# B138X.net
KiCad netlist of a schematic drawn in EAGLE
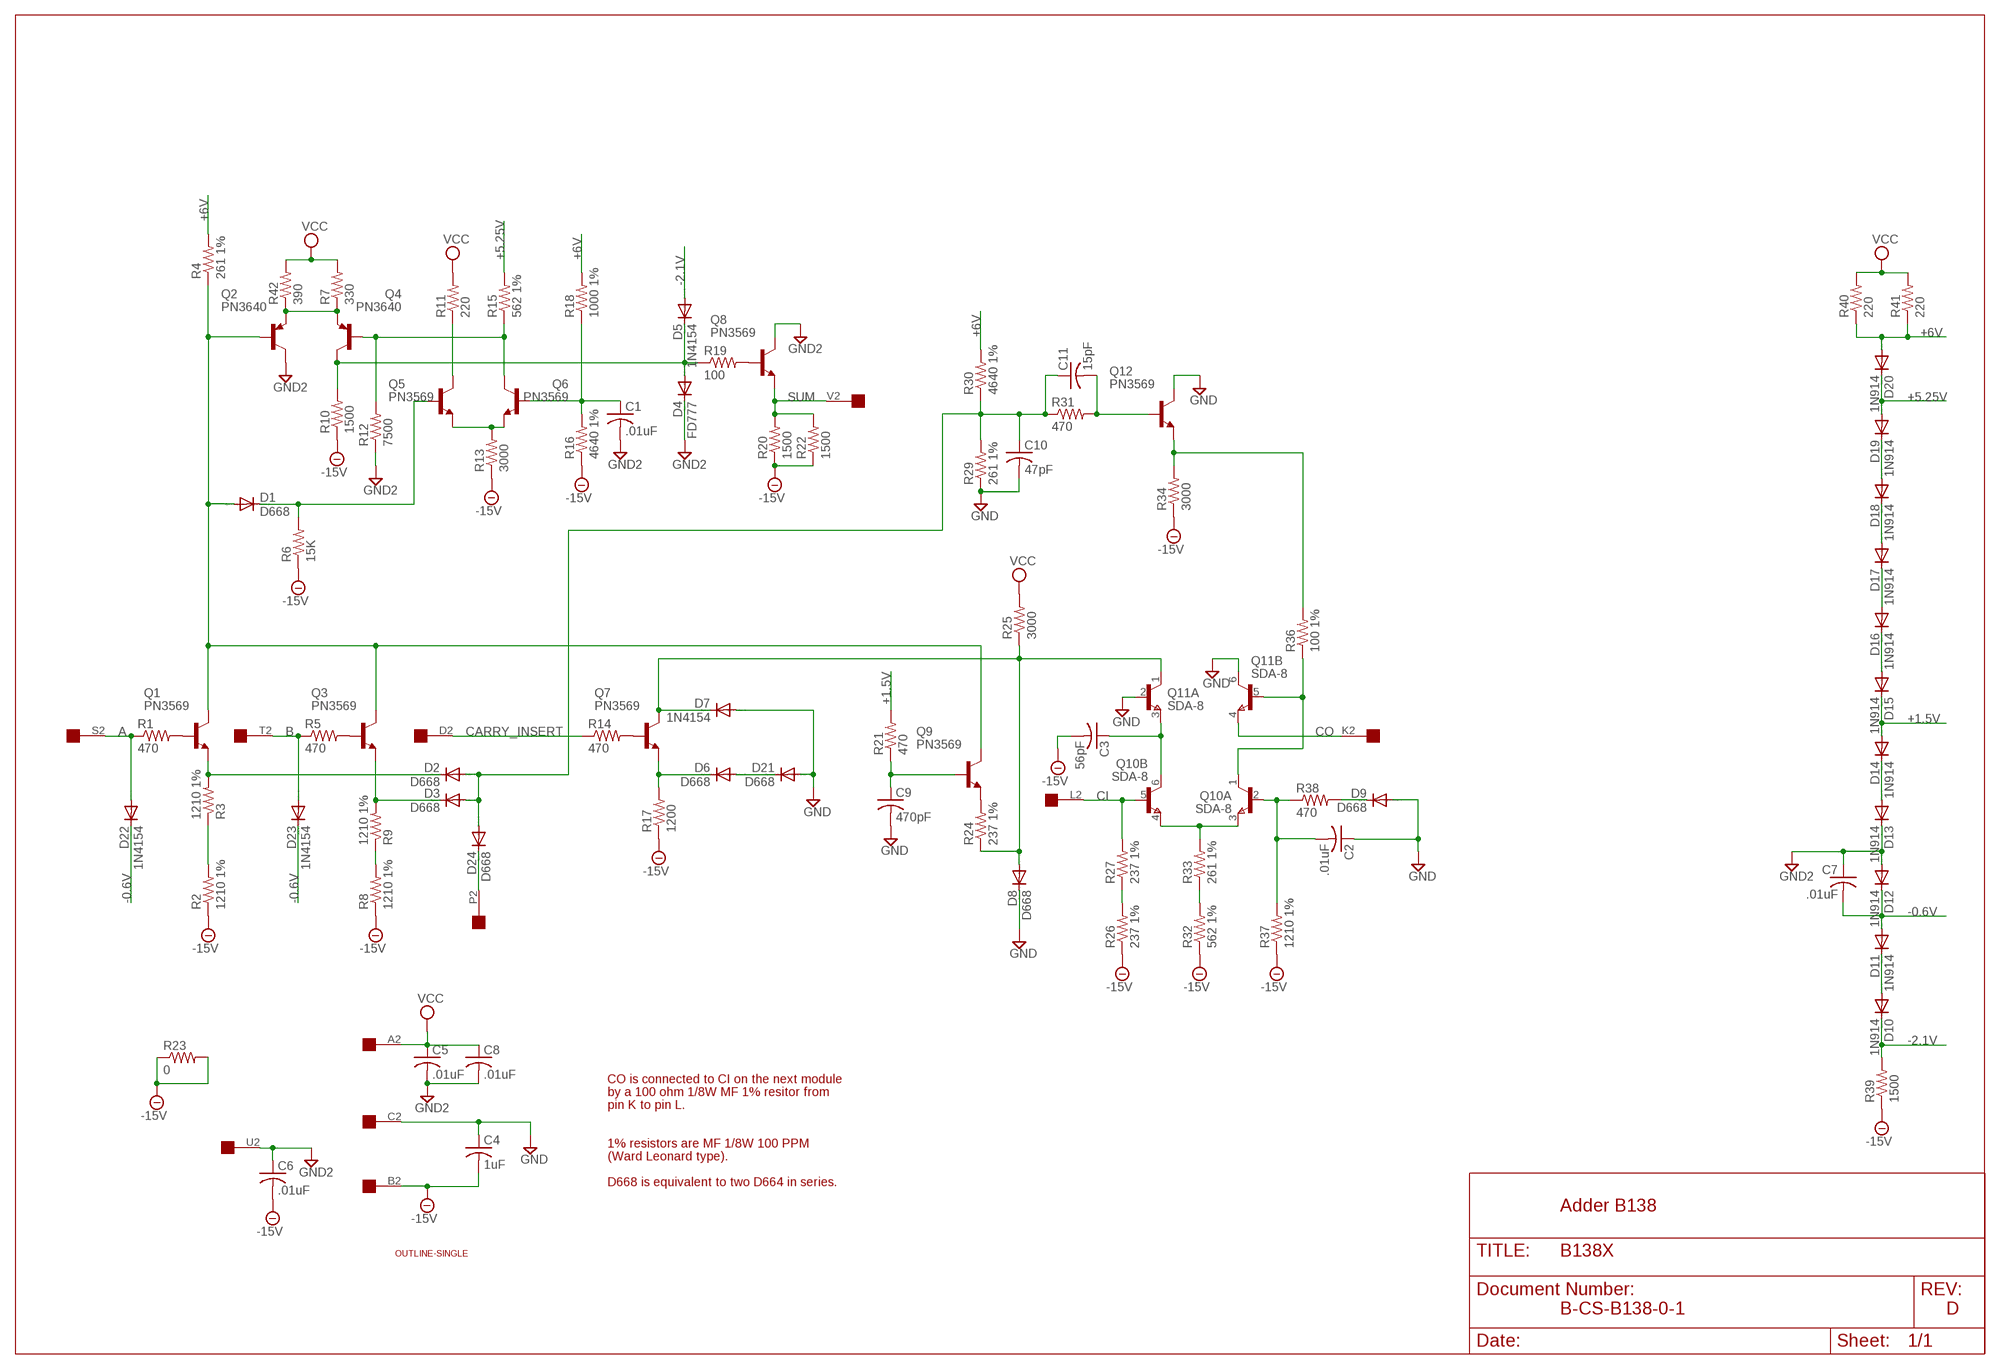
[diagram p0: schematic, sheet 1]

(export (version "E")
  (design (tool "Eeschema 10.0.6"))
  (components
    (comp (ref "C1")
      (value ".01uF")
      (footprint "eagle-import:C063-025X075")
      (libsource (lib "eagle-import") (part "C-US"))
    )
    (comp (ref "C2")
      (value ".01uF")
      (footprint "eagle-import:C063-025X075")
      (libsource (lib "eagle-import") (part "C-US"))
    )
    (comp (ref "C3")
      (value "56pF")
      (footprint "eagle-import:C063-025X075")
      (libsource (lib "eagle-import") (part "C-US"))
    )
    (comp (ref "C4")
      (value "1uF")
      (footprint "eagle-import:C102-043X133")
      (libsource (lib "eagle-import") (part "C-US102-043X133"))
    )
    (comp (ref "C5")
      (value ".01uF")
      (footprint "eagle-import:C063-025X075")
      (libsource (lib "eagle-import") (part "C-US"))
    )
    (comp (ref "C6")
      (value ".01uF")
      (footprint "eagle-import:C063-025X075")
      (libsource (lib "eagle-import") (part "C-US"))
    )
    (comp (ref "C7")
      (value ".01uF")
      (footprint "eagle-import:C063-025X075")
      (libsource (lib "eagle-import") (part "C-US"))
    )
    (comp (ref "C8")
      (value ".01uF")
      (footprint "eagle-import:C063-025X075")
      (libsource (lib "eagle-import") (part "C-US"))
    )
    (comp (ref "C9")
      (value "470pF")
      (footprint "eagle-import:C063-025X075")
      (libsource (lib "eagle-import") (part "C-US"))
    )
    (comp (ref "C10")
      (value "47pF")
      (footprint "eagle-import:C063-025X075")
      (libsource (lib "eagle-import") (part "C-US"))
    )
    (comp (ref "C11")
      (value "15pF")
      (footprint "eagle-import:C063-025X075")
      (libsource (lib "eagle-import") (part "C-US"))
    )
    (comp (ref "D1")
      (value "D668")
      (footprint "eagle-import:DO35-10")
      (libsource (lib "eagle-import") (part "DIODE-DO35-10"))
    )
    (comp (ref "D2")
      (value "D668")
      (footprint "eagle-import:DO35-10")
      (libsource (lib "eagle-import") (part "DIODE-DO35-10"))
    )
    (comp (ref "D3")
      (value "D668")
      (footprint "eagle-import:DO35-10")
      (libsource (lib "eagle-import") (part "DIODE-DO35-10"))
    )
    (comp (ref "D4")
      (value "FD777")
      (footprint "eagle-import:DO35-10")
      (libsource (lib "eagle-import") (part "DIODE-DO35-10"))
    )
    (comp (ref "D5")
      (value "1N4154")
      (footprint "eagle-import:DO35-10")
      (libsource (lib "eagle-import") (part "DIODE-DO35-10"))
    )
    (comp (ref "D6")
      (value "D668")
      (footprint "eagle-import:DO35-10")
      (libsource (lib "eagle-import") (part "DIODE-DO35-10"))
    )
    (comp (ref "D7")
      (value "1N4154")
      (footprint "eagle-import:DO35-10")
      (libsource (lib "eagle-import") (part "DIODE-DO35-10"))
    )
    (comp (ref "D8")
      (value "D668")
      (footprint "eagle-import:DO35-10")
      (libsource (lib "eagle-import") (part "DIODE-DO35-10"))
    )
    (comp (ref "D9")
      (value "D668")
      (footprint "eagle-import:DO35-10")
      (libsource (lib "eagle-import") (part "DIODE-DO35-10"))
    )
    (comp (ref "D10")
      (value "1N914")
      (footprint "eagle-import:DO35-10")
      (libsource (lib "eagle-import") (part "DIODE-DO35-10"))
    )
    (comp (ref "D11")
      (value "1N914")
      (footprint "eagle-import:DO35-10")
      (libsource (lib "eagle-import") (part "DIODE-DO35-10"))
    )
    (comp (ref "D12")
      (value "1N914")
      (footprint "eagle-import:DO35-10")
      (libsource (lib "eagle-import") (part "DIODE-DO35-10"))
    )
    (comp (ref "D13")
      (value "1N914")
      (footprint "eagle-import:DO35-10")
      (libsource (lib "eagle-import") (part "DIODE-DO35-10"))
    )
    (comp (ref "D14")
      (value "1N914")
      (footprint "eagle-import:DO35-10")
      (libsource (lib "eagle-import") (part "DIODE-DO35-10"))
    )
    (comp (ref "D15")
      (value "1N914")
      (footprint "eagle-import:DO35-10")
      (libsource (lib "eagle-import") (part "DIODE-DO35-10"))
    )
    (comp (ref "D16")
      (value "1N914")
      (footprint "eagle-import:DO35-10")
      (libsource (lib "eagle-import") (part "DIODE-DO35-10"))
    )
    (comp (ref "D17")
      (value "1N914")
      (footprint "eagle-import:DO35-10")
      (libsource (lib "eagle-import") (part "DIODE-DO35-10"))
    )
    (comp (ref "D18")
      (value "1N914")
      (footprint "eagle-import:DO35-10")
      (libsource (lib "eagle-import") (part "DIODE-DO35-10"))
    )
    (comp (ref "D19")
      (value "1N914")
      (footprint "eagle-import:DO35-10")
      (libsource (lib "eagle-import") (part "DIODE-DO35-10"))
    )
    (comp (ref "D20")
      (value "1N914")
      (footprint "eagle-import:DO35-10")
      (libsource (lib "eagle-import") (part "DIODE-DO35-10"))
    )
    (comp (ref "D21")
      (value "D668")
      (footprint "eagle-import:DO35-10")
      (libsource (lib "eagle-import") (part "DIODE-DO35-10"))
    )
    (comp (ref "D22")
      (value "1N4154")
      (footprint "eagle-import:DO35-10")
      (libsource (lib "eagle-import") (part "DIODE-DO35-10"))
    )
    (comp (ref "D23")
      (value "1N4154")
      (footprint "eagle-import:DO35-10")
      (libsource (lib "eagle-import") (part "DIODE-DO35-10"))
    )
    (comp (ref "D24")
      (value "D668")
      (footprint "eagle-import:DO35-10")
      (libsource (lib "eagle-import") (part "DIODE-DO35-10"))
    )
    (comp (ref "Q1")
      (value "PN3569")
      (footprint "eagle-import:TO5")
      (libsource (lib "eagle-import") (part "-NPN-TO5"))
    )
    (comp (ref "Q2")
      (value "PN3640")
      (footprint "eagle-import:TO5")
      (libsource (lib "eagle-import") (part "-PNP-TO5"))
    )
    (comp (ref "Q3")
      (value "PN3569")
      (footprint "eagle-import:TO5")
      (libsource (lib "eagle-import") (part "-NPN-TO5"))
    )
    (comp (ref "Q4")
      (value "PN3640")
      (footprint "eagle-import:TO5")
      (libsource (lib "eagle-import") (part "-PNP-TO5"))
    )
    (comp (ref "Q5")
      (value "PN3569")
      (footprint "eagle-import:TO5")
      (libsource (lib "eagle-import") (part "-NPN-TO5"))
    )
    (comp (ref "Q6")
      (value "PN3569")
      (footprint "eagle-import:TO5")
      (libsource (lib "eagle-import") (part "-NPN-TO5"))
    )
    (comp (ref "Q7")
      (value "PN3569")
      (footprint "eagle-import:TO5")
      (libsource (lib "eagle-import") (part "-NPN-TO5"))
    )
    (comp (ref "Q8")
      (value "PN3569")
      (footprint "eagle-import:TO5")
      (libsource (lib "eagle-import") (part "-NPN-TO5"))
    )
    (comp (ref "Q9")
      (value "PN3569")
      (footprint "eagle-import:TO5")
      (libsource (lib "eagle-import") (part "-NPN-TO5"))
    )
    (comp (ref "Q10")
      (value "SDA-8")
      (footprint "eagle-import:TO78")
      (libsource (lib "eagle-import") (part "MAT-02H"))
    )
    (comp (ref "Q11")
      (value "SDA-8")
      (footprint "eagle-import:TO78")
      (libsource (lib "eagle-import") (part "MAT-02H"))
    )
    (comp (ref "Q12")
      (value "PN3569")
      (footprint "eagle-import:TO5")
      (libsource (lib "eagle-import") (part "-NPN-TO5"))
    )
    (comp (ref "R1")
      (value "470")
      (footprint "eagle-import:0207_10")
      (libsource (lib "eagle-import") (part "R-US_0207/10"))
    )
    (comp (ref "R2")
      (value "1210 1%")
      (footprint "eagle-import:0207_15")
      (libsource (lib "eagle-import") (part "R-US_0207/15"))
    )
    (comp (ref "R3")
      (value "1210 1%")
      (footprint "eagle-import:0207_15")
      (libsource (lib "eagle-import") (part "R-US_0207/15"))
    )
    (comp (ref "R4")
      (value "261 1%")
      (footprint "eagle-import:0207_15")
      (libsource (lib "eagle-import") (part "R-US_0207/15"))
    )
    (comp (ref "R5")
      (value "470")
      (footprint "eagle-import:0207_10")
      (libsource (lib "eagle-import") (part "R-US_0207/10"))
    )
    (comp (ref "R6")
      (value "15K")
      (footprint "eagle-import:0207_10")
      (libsource (lib "eagle-import") (part "R-US_0207/10"))
    )
    (comp (ref "R7")
      (value "330")
      (footprint "eagle-import:0207_10")
      (libsource (lib "eagle-import") (part "R-US_0207/10"))
    )
    (comp (ref "R8")
      (value "1210 1%")
      (footprint "eagle-import:0207_15")
      (libsource (lib "eagle-import") (part "R-US_0207/15"))
    )
    (comp (ref "R9")
      (value "1210 1%")
      (footprint "eagle-import:0207_15")
      (libsource (lib "eagle-import") (part "R-US_0207/15"))
    )
    (comp (ref "R10")
      (value "1500")
      (footprint "eagle-import:0207_10")
      (libsource (lib "eagle-import") (part "R-US_0207/10"))
    )
    (comp (ref "R11")
      (value "220")
      (footprint "eagle-import:0207_10")
      (libsource (lib "eagle-import") (part "R-US_0207/10"))
    )
    (comp (ref "R12")
      (value "7500")
      (footprint "eagle-import:0207_10")
      (libsource (lib "eagle-import") (part "R-US_0207/10"))
    )
    (comp (ref "R13")
      (value "3000")
      (footprint "eagle-import:0207_10")
      (libsource (lib "eagle-import") (part "R-US_0207/10"))
    )
    (comp (ref "R14")
      (value "470")
      (footprint "eagle-import:0207_10")
      (libsource (lib "eagle-import") (part "R-US_0207/10"))
    )
    (comp (ref "R15")
      (value "562 1%")
      (footprint "eagle-import:0207_15")
      (libsource (lib "eagle-import") (part "R-US_0207/15"))
    )
    (comp (ref "R16")
      (value "4640 1%")
      (footprint "eagle-import:0207_15")
      (libsource (lib "eagle-import") (part "R-US_0207/15"))
    )
    (comp (ref "R17")
      (value "1200")
      (footprint "eagle-import:0207_10")
      (libsource (lib "eagle-import") (part "R-US_0207/10"))
    )
    (comp (ref "R18")
      (value "1000 1%")
      (footprint "eagle-import:0207_15")
      (libsource (lib "eagle-import") (part "R-US_0207/15"))
    )
    (comp (ref "R19")
      (value "100")
      (footprint "eagle-import:0207_10")
      (libsource (lib "eagle-import") (part "R-US_0207/10"))
    )
    (comp (ref "R20")
      (value "1500")
      (footprint "eagle-import:0207_10")
      (libsource (lib "eagle-import") (part "R-US_0207/10"))
    )
    (comp (ref "R21")
      (value "470")
      (footprint "eagle-import:0207_10")
      (libsource (lib "eagle-import") (part "R-US_0207/10"))
    )
    (comp (ref "R22")
      (value "1500")
      (footprint "eagle-import:0207_10")
      (libsource (lib "eagle-import") (part "R-US_0207/10"))
    )
    (comp (ref "R23")
      (value "0")
      (footprint "eagle-import:0207_10")
      (libsource (lib "eagle-import") (part "R-US_0207/10"))
    )
    (comp (ref "R24")
      (value "237 1%")
      (footprint "eagle-import:0207_15")
      (libsource (lib "eagle-import") (part "R-US_0207/15"))
    )
    (comp (ref "R25")
      (value "3000")
      (footprint "eagle-import:0207_10")
      (libsource (lib "eagle-import") (part "R-US_0207/10"))
    )
    (comp (ref "R26")
      (value "237 1%")
      (footprint "eagle-import:0207_15")
      (libsource (lib "eagle-import") (part "R-US_0207/15"))
    )
    (comp (ref "R27")
      (value "237 1%")
      (footprint "eagle-import:0207_15")
      (libsource (lib "eagle-import") (part "R-US_0207/15"))
    )
    (comp (ref "R29")
      (value "261 1%")
      (footprint "eagle-import:0207_15")
      (libsource (lib "eagle-import") (part "R-US_0207/15"))
    )
    (comp (ref "R30")
      (value "4640 1%")
      (footprint "eagle-import:0207_15")
      (libsource (lib "eagle-import") (part "R-US_0207/15"))
    )
    (comp (ref "R31")
      (value "470")
      (footprint "eagle-import:0207_10")
      (libsource (lib "eagle-import") (part "R-US_0207/10"))
    )
    (comp (ref "R32")
      (value "562 1%")
      (footprint "eagle-import:0207_15")
      (libsource (lib "eagle-import") (part "R-US_0207/15"))
    )
    (comp (ref "R33")
      (value "261 1%")
      (footprint "eagle-import:0207_15")
      (libsource (lib "eagle-import") (part "R-US_0207/15"))
    )
    (comp (ref "R34")
      (value "3000")
      (footprint "eagle-import:0207_10")
      (libsource (lib "eagle-import") (part "R-US_0207/10"))
    )
    (comp (ref "R36")
      (value "100 1%")
      (footprint "eagle-import:0207_15")
      (libsource (lib "eagle-import") (part "R-US_0207/15"))
    )
    (comp (ref "R37")
      (value "1210 1%")
      (footprint "eagle-import:0207_15")
      (libsource (lib "eagle-import") (part "R-US_0207/15"))
    )
    (comp (ref "R38")
      (value "470")
      (footprint "eagle-import:0207_10")
      (libsource (lib "eagle-import") (part "R-US_0207/10"))
    )
    (comp (ref "R39")
      (value "1500")
      (footprint "eagle-import:0207_10")
      (libsource (lib "eagle-import") (part "R-US_0207/10"))
    )
    (comp (ref "R40")
      (value "220")
      (footprint "eagle-import:0207_10")
      (libsource (lib "eagle-import") (part "R-US_0207/10"))
    )
    (comp (ref "R41")
      (value "220")
      (footprint "eagle-import:0207_10")
      (libsource (lib "eagle-import") (part "R-US_0207/10"))
    )
    (comp (ref "R42")
      (value "390")
      (footprint "eagle-import:0207_10")
      (libsource (lib "eagle-import") (part "R-US_0207/10"))
    )
    (comp (ref "U$1")
      (value "OUTLINE-SINGLE")
      (footprint "eagle-import:SINGLE")
      (libsource (lib "eagle-import") (part "OUTLINE-SINGLE"))
    )
    (comp (ref "U$2")
      (value "EDGE-1")
      (footprint "eagle-import:EDGE-CON1")
      (libsource (lib "eagle-import") (part "EDGE-1"))
    )
  )
  (nets
    (net (code "1") (name "-15V") (class "Default")
      (node (ref "C3") (pin "2") (pinfunction "2_2") (pintype "passive"))
      (node (ref "C4") (pin "2") (pinfunction "2_2") (pintype "passive"))
      (node (ref "C6") (pin "2") (pinfunction "2_2") (pintype "passive"))
      (node (ref "R10") (pin "1") (pinfunction "1_1") (pintype "passive"))
      (node (ref "R13") (pin "1") (pinfunction "1_1") (pintype "passive"))
      (node (ref "R16") (pin "1") (pinfunction "1_1") (pintype "passive"))
      (node (ref "R17") (pin "1") (pinfunction "1_1") (pintype "passive"))
      (node (ref "R2") (pin "1") (pinfunction "1_1") (pintype "passive"))
      (node (ref "R20") (pin "1") (pinfunction "1_1") (pintype "passive"))
      (node (ref "R22") (pin "1") (pinfunction "1_1") (pintype "passive"))
      (node (ref "R23") (pin "1") (pinfunction "1_1") (pintype "passive"))
      (node (ref "R23") (pin "2") (pinfunction "2_2") (pintype "passive"))
      (node (ref "R26") (pin "1") (pinfunction "1_1") (pintype "passive"))
      (node (ref "R32") (pin "1") (pinfunction "1_1") (pintype "passive"))
      (node (ref "R34") (pin "1") (pinfunction "1_1") (pintype "passive"))
      (node (ref "R37") (pin "1") (pinfunction "1_1") (pintype "passive"))
      (node (ref "R39") (pin "1") (pinfunction "1_1") (pintype "passive"))
      (node (ref "R6") (pin "1") (pinfunction "1_1") (pintype "passive"))
      (node (ref "R8") (pin "1") (pinfunction "1_1") (pintype "passive"))
      (node (ref "U$2") (pin "B2") (pinfunction "1_B2") (pintype "bidirectional"))
    )
    (net (code "2") (name "/+1.5V") (class "Default")
      (node (ref "D14") (pin "A") (pinfunction "A_A") (pintype "passive"))
      (node (ref "D15") (pin "C") (pinfunction "C_C") (pintype "passive"))
      (node (ref "R21") (pin "2") (pinfunction "2_2") (pintype "passive"))
    )
    (net (code "3") (name "/+5.25V") (class "Default")
      (node (ref "D19") (pin "A") (pinfunction "A_A") (pintype "passive"))
      (node (ref "D20") (pin "C") (pinfunction "C_C") (pintype "passive"))
      (node (ref "R15") (pin "2") (pinfunction "2_2") (pintype "passive"))
    )
    (net (code "4") (name "/+6V") (class "Default")
      (node (ref "D20") (pin "A") (pinfunction "A_A") (pintype "passive"))
      (node (ref "R18") (pin "2") (pinfunction "2_2") (pintype "passive"))
      (node (ref "R30") (pin "2") (pinfunction "2_2") (pintype "passive"))
      (node (ref "R4") (pin "2") (pinfunction "2_2") (pintype "passive"))
      (node (ref "R40") (pin "1") (pinfunction "1_1") (pintype "passive"))
      (node (ref "R41") (pin "1") (pinfunction "1_1") (pintype "passive"))
    )
    (net (code "5") (name "/-0.6V") (class "Default")
      (node (ref "C7") (pin "2") (pinfunction "2_2") (pintype "passive"))
      (node (ref "D11") (pin "A") (pinfunction "A_A") (pintype "passive"))
      (node (ref "D12") (pin "C") (pinfunction "C_C") (pintype "passive"))
      (node (ref "D22") (pin "C") (pinfunction "C_C") (pintype "passive"))
      (node (ref "D23") (pin "C") (pinfunction "C_C") (pintype "passive"))
    )
    (net (code "6") (name "/-2.1V") (class "Default")
      (node (ref "D10") (pin "C") (pinfunction "C_C") (pintype "passive"))
      (node (ref "D5") (pin "A") (pinfunction "A_A") (pintype "passive"))
      (node (ref "R39") (pin "2") (pinfunction "2_2") (pintype "passive"))
    )
    (net (code "7") (name "/A") (class "Default")
      (node (ref "D22") (pin "A") (pinfunction "A_A") (pintype "passive"))
      (node (ref "R1") (pin "1") (pinfunction "1_1") (pintype "passive"))
      (node (ref "U$2") (pin "S2") (pinfunction "1_S2") (pintype "bidirectional"))
    )
    (net (code "8") (name "/B") (class "Default")
      (node (ref "D23") (pin "A") (pinfunction "A_A") (pintype "passive"))
      (node (ref "R5") (pin "1") (pinfunction "1_1") (pintype "passive"))
      (node (ref "U$2") (pin "T2") (pinfunction "1_T2") (pintype "bidirectional"))
    )
    (net (code "9") (name "/CARRY_INSERT") (class "Default")
      (node (ref "R14") (pin "1") (pinfunction "1_1") (pintype "passive"))
      (node (ref "U$2") (pin "D2") (pinfunction "1_D2") (pintype "bidirectional"))
    )
    (net (code "10") (name "/CI") (class "Default")
      (node (ref "Q10") (pin "5") (pinfunction "B_5") (pintype "passive"))
      (node (ref "R27") (pin "2") (pinfunction "2_2") (pintype "passive"))
      (node (ref "U$2") (pin "L2") (pinfunction "1_L2") (pintype "bidirectional"))
    )
    (net (code "11") (name "/CO") (class "Default")
      (node (ref "Q11") (pin "4") (pinfunction "E_4") (pintype "passive"))
      (node (ref "U$2") (pin "K2") (pinfunction "1_K2") (pintype "bidirectional"))
    )
    (net (code "12") (name "/SUM") (class "Default")
      (node (ref "Q8") (pin "1") (pinfunction "E_1") (pintype "passive"))
      (node (ref "R20") (pin "2") (pinfunction "2_2") (pintype "passive"))
      (node (ref "R22") (pin "2") (pinfunction "2_2") (pintype "passive"))
      (node (ref "U$2") (pin "V2") (pinfunction "1_V2") (pintype "bidirectional"))
    )
    (net (code "13") (name "GND") (class "Default")
      (node (ref "C10") (pin "2") (pinfunction "2_2") (pintype "passive"))
      (node (ref "C2") (pin "1") (pinfunction "1_1") (pintype "passive"))
      (node (ref "C4") (pin "1") (pinfunction "1_1") (pintype "passive"))
      (node (ref "C9") (pin "2") (pinfunction "2_2") (pintype "passive"))
      (node (ref "D21") (pin "A") (pinfunction "A_A") (pintype "passive"))
      (node (ref "D7") (pin "A") (pinfunction "A_A") (pintype "passive"))
      (node (ref "D8") (pin "C") (pinfunction "C_C") (pintype "passive"))
      (node (ref "D9") (pin "A") (pinfunction "A_A") (pintype "passive"))
      (node (ref "Q11") (pin "2") (pinfunction "B_2") (pintype "passive"))
      (node (ref "Q11") (pin "6") (pinfunction "C_6") (pintype "passive"))
      (node (ref "Q12") (pin "3") (pinfunction "C_3") (pintype "passive"))
      (node (ref "R29") (pin "1") (pinfunction "1_1") (pintype "passive"))
      (node (ref "U$2") (pin "C2") (pinfunction "1_C2") (pintype "bidirectional"))
    )
    (net (code "14") (name "GND2") (class "Default")
      (node (ref "C1") (pin "2") (pinfunction "2_2") (pintype "passive"))
      (node (ref "C5") (pin "2") (pinfunction "2_2") (pintype "passive"))
      (node (ref "C6") (pin "1") (pinfunction "1_1") (pintype "passive"))
      (node (ref "C7") (pin "1") (pinfunction "1_1") (pintype "passive"))
      (node (ref "C8") (pin "2") (pinfunction "2_2") (pintype "passive"))
      (node (ref "D12") (pin "A") (pinfunction "A_A") (pintype "passive"))
      (node (ref "D13") (pin "C") (pinfunction "C_C") (pintype "passive"))
      (node (ref "D4") (pin "C") (pinfunction "C_C") (pintype "passive"))
      (node (ref "Q2") (pin "3") (pinfunction "C_3") (pintype "passive"))
      (node (ref "Q8") (pin "3") (pinfunction "C_3") (pintype "passive"))
      (node (ref "R12") (pin "1") (pinfunction "1_1") (pintype "passive"))
      (node (ref "U$2") (pin "U2") (pinfunction "1_U2") (pintype "bidirectional"))
    )
    (net (code "15") (name "Net-(C10-Pad1)") (class "Default")
      (node (ref "C10") (pin "1") (pinfunction "1_1") (pintype "passive"))
      (node (ref "C11") (pin "1") (pinfunction "1_1") (pintype "passive"))
      (node (ref "D2") (pin "A") (pinfunction "A_A") (pintype "passive"))
      (node (ref "D24") (pin "A") (pinfunction "A_A") (pintype "passive"))
      (node (ref "D3") (pin "A") (pinfunction "A_A") (pintype "passive"))
      (node (ref "R29") (pin "2") (pinfunction "2_2") (pintype "passive"))
      (node (ref "R30") (pin "1") (pinfunction "1_1") (pintype "passive"))
      (node (ref "R31") (pin "1") (pinfunction "1_1") (pintype "passive"))
    )
    (net (code "16") (name "Net-(D9-PadC)") (class "Default")
      (node (ref "D9") (pin "C") (pinfunction "C_C") (pintype "passive"))
      (node (ref "R38") (pin "2") (pinfunction "2_2") (pintype "passive"))
    )
    (net (code "17") (name "Net-(D10-PadA)") (class "Default")
      (node (ref "D10") (pin "A") (pinfunction "A_A") (pintype "passive"))
      (node (ref "D11") (pin "C") (pinfunction "C_C") (pintype "passive"))
    )
    (net (code "18") (name "Net-(D13-PadA)") (class "Default")
      (node (ref "D13") (pin "A") (pinfunction "A_A") (pintype "passive"))
      (node (ref "D14") (pin "C") (pinfunction "C_C") (pintype "passive"))
    )
    (net (code "19") (name "Net-(D15-PadA)") (class "Default")
      (node (ref "D15") (pin "A") (pinfunction "A_A") (pintype "passive"))
      (node (ref "D16") (pin "C") (pinfunction "C_C") (pintype "passive"))
    )
    (net (code "20") (name "Net-(D16-PadA)") (class "Default")
      (node (ref "D16") (pin "A") (pinfunction "A_A") (pintype "passive"))
      (node (ref "D17") (pin "C") (pinfunction "C_C") (pintype "passive"))
    )
    (net (code "21") (name "Net-(D17-PadA)") (class "Default")
      (node (ref "D17") (pin "A") (pinfunction "A_A") (pintype "passive"))
      (node (ref "D18") (pin "C") (pinfunction "C_C") (pintype "passive"))
    )
    (net (code "22") (name "Net-(D18-PadA)") (class "Default")
      (node (ref "D18") (pin "A") (pinfunction "A_A") (pintype "passive"))
      (node (ref "D19") (pin "C") (pinfunction "C_C") (pintype "passive"))
    )
    (net (code "23") (name "Net-(D21-PadC)") (class "Default")
      (node (ref "D21") (pin "C") (pinfunction "C_C") (pintype "passive"))
      (node (ref "D6") (pin "A") (pinfunction "A_A") (pintype "passive"))
    )
    (net (code "24") (name "Net-(Q1-B)") (class "Default")
      (node (ref "Q1") (pin "2") (pinfunction "B_2") (pintype "passive"))
      (node (ref "R1") (pin "2") (pinfunction "2_2") (pintype "passive"))
    )
    (net (code "25") (name "Net-(Q1-C)") (class "Default")
      (node (ref "D1") (pin "A") (pinfunction "A_A") (pintype "passive"))
      (node (ref "Q1") (pin "3") (pinfunction "C_3") (pintype "passive"))
      (node (ref "Q2") (pin "2") (pinfunction "B_2") (pintype "passive"))
      (node (ref "Q3") (pin "3") (pinfunction "C_3") (pintype "passive"))
      (node (ref "Q9") (pin "3") (pinfunction "C_3") (pintype "passive"))
      (node (ref "R4") (pin "1") (pinfunction "1_1") (pintype "passive"))
    )
    (net (code "26") (name "Net-(Q1-E)") (class "Default")
      (node (ref "D2") (pin "C") (pinfunction "C_C") (pintype "passive"))
      (node (ref "Q1") (pin "1") (pinfunction "E_1") (pintype "passive"))
      (node (ref "R3") (pin "2") (pinfunction "2_2") (pintype "passive"))
    )
    (net (code "27") (name "Net-(Q2-E)") (class "Default")
      (node (ref "Q2") (pin "1") (pinfunction "E_1") (pintype "passive"))
      (node (ref "Q4") (pin "1") (pinfunction "E_1") (pintype "passive"))
      (node (ref "R42") (pin "1") (pinfunction "1_1") (pintype "passive"))
      (node (ref "R7") (pin "1") (pinfunction "1_1") (pintype "passive"))
    )
    (net (code "28") (name "Net-(Q3-B)") (class "Default")
      (node (ref "Q3") (pin "2") (pinfunction "B_2") (pintype "passive"))
      (node (ref "R5") (pin "2") (pinfunction "2_2") (pintype "passive"))
    )
    (net (code "29") (name "Net-(Q3-E)") (class "Default")
      (node (ref "D3") (pin "C") (pinfunction "C_C") (pintype "passive"))
      (node (ref "Q3") (pin "1") (pinfunction "E_1") (pintype "passive"))
      (node (ref "R9") (pin "2") (pinfunction "2_2") (pintype "passive"))
    )
    (net (code "30") (name "Net-(Q4-B)") (class "Default")
      (node (ref "Q4") (pin "2") (pinfunction "B_2") (pintype "passive"))
      (node (ref "Q6") (pin "3") (pinfunction "C_3") (pintype "passive"))
      (node (ref "R12") (pin "2") (pinfunction "2_2") (pintype "passive"))
      (node (ref "R15") (pin "1") (pinfunction "1_1") (pintype "passive"))
    )
    (net (code "31") (name "Net-(Q4-C)") (class "Default")
      (node (ref "D4") (pin "A") (pinfunction "A_A") (pintype "passive"))
      (node (ref "D5") (pin "C") (pinfunction "C_C") (pintype "passive"))
      (node (ref "Q4") (pin "3") (pinfunction "C_3") (pintype "passive"))
      (node (ref "R10") (pin "2") (pinfunction "2_2") (pintype "passive"))
      (node (ref "R19") (pin "1") (pinfunction "1_1") (pintype "passive"))
    )
    (net (code "32") (name "Net-(Q5-B)") (class "Default")
      (node (ref "D1") (pin "C") (pinfunction "C_C") (pintype "passive"))
      (node (ref "Q5") (pin "2") (pinfunction "B_2") (pintype "passive"))
      (node (ref "R6") (pin "2") (pinfunction "2_2") (pintype "passive"))
    )
    (net (code "33") (name "Net-(Q5-C)") (class "Default")
      (node (ref "Q5") (pin "3") (pinfunction "C_3") (pintype "passive"))
      (node (ref "R11") (pin "1") (pinfunction "1_1") (pintype "passive"))
    )
    (net (code "34") (name "Net-(Q5-E)") (class "Default")
      (node (ref "Q5") (pin "1") (pinfunction "E_1") (pintype "passive"))
      (node (ref "Q6") (pin "1") (pinfunction "E_1") (pintype "passive"))
      (node (ref "R13") (pin "2") (pinfunction "2_2") (pintype "passive"))
    )
    (net (code "35") (name "Net-(Q6-B)") (class "Default")
      (node (ref "C1") (pin "1") (pinfunction "1_1") (pintype "passive"))
      (node (ref "Q6") (pin "2") (pinfunction "B_2") (pintype "passive"))
      (node (ref "R16") (pin "2") (pinfunction "2_2") (pintype "passive"))
      (node (ref "R18") (pin "1") (pinfunction "1_1") (pintype "passive"))
    )
    (net (code "36") (name "Net-(Q7-B)") (class "Default")
      (node (ref "Q7") (pin "2") (pinfunction "B_2") (pintype "passive"))
      (node (ref "R14") (pin "2") (pinfunction "2_2") (pintype "passive"))
    )
    (net (code "37") (name "Net-(Q7-E)") (class "Default")
      (node (ref "D6") (pin "C") (pinfunction "C_C") (pintype "passive"))
      (node (ref "Q7") (pin "1") (pinfunction "E_1") (pintype "passive"))
      (node (ref "R17") (pin "2") (pinfunction "2_2") (pintype "passive"))
    )
    (net (code "38") (name "Net-(Q8-B)") (class "Default")
      (node (ref "Q8") (pin "2") (pinfunction "B_2") (pintype "passive"))
      (node (ref "R19") (pin "2") (pinfunction "2_2") (pintype "passive"))
    )
    (net (code "39") (name "Net-(Q9-B)") (class "Default")
      (node (ref "C9") (pin "1") (pinfunction "1_1") (pintype "passive"))
      (node (ref "Q9") (pin "2") (pinfunction "B_2") (pintype "passive"))
      (node (ref "R21") (pin "1") (pinfunction "1_1") (pintype "passive"))
    )
    (net (code "40") (name "Net-(Q9-E)") (class "Default")
      (node (ref "Q9") (pin "1") (pinfunction "E_1") (pintype "passive"))
      (node (ref "R24") (pin "2") (pinfunction "2_2") (pintype "passive"))
    )
    (net (code "41") (name "Net-(Q10A-B)") (class "Default")
      (node (ref "C2") (pin "2") (pinfunction "2_2") (pintype "passive"))
      (node (ref "Q10") (pin "2") (pinfunction "B_2") (pintype "passive"))
      (node (ref "R37") (pin "2") (pinfunction "2_2") (pintype "passive"))
      (node (ref "R38") (pin "1") (pinfunction "1_1") (pintype "passive"))
    )
    (net (code "42") (name "Net-(Q10A-C)") (class "Default")
      (node (ref "Q10") (pin "1") (pinfunction "C_1") (pintype "passive"))
      (node (ref "Q11") (pin "5") (pinfunction "B_5") (pintype "passive"))
      (node (ref "R36") (pin "1") (pinfunction "1_1") (pintype "passive"))
    )
    (net (code "43") (name "Net-(Q10A-E)") (class "Default")
      (node (ref "Q10") (pin "3") (pinfunction "E_3") (pintype "passive"))
      (node (ref "Q10") (pin "4") (pinfunction "E_4") (pintype "passive"))
      (node (ref "R33") (pin "2") (pinfunction "2_2") (pintype "passive"))
    )
    (net (code "44") (name "Net-(Q10B-C)") (class "Default")
      (node (ref "C3") (pin "1") (pinfunction "1_1") (pintype "passive"))
      (node (ref "Q10") (pin "6") (pinfunction "C_6") (pintype "passive"))
      (node (ref "Q11") (pin "3") (pinfunction "E_3") (pintype "passive"))
    )
    (net (code "45") (name "Net-(Q11A-C)") (class "Default")
      (node (ref "D7") (pin "C") (pinfunction "C_C") (pintype "passive"))
      (node (ref "D8") (pin "A") (pinfunction "A_A") (pintype "passive"))
      (node (ref "Q11") (pin "1") (pinfunction "C_1") (pintype "passive"))
      (node (ref "Q7") (pin "3") (pinfunction "C_3") (pintype "passive"))
      (node (ref "R24") (pin "1") (pinfunction "1_1") (pintype "passive"))
      (node (ref "R25") (pin "1") (pinfunction "1_1") (pintype "passive"))
    )
    (net (code "46") (name "Net-(Q12-B)") (class "Default")
      (node (ref "C11") (pin "2") (pinfunction "2_2") (pintype "passive"))
      (node (ref "Q12") (pin "2") (pinfunction "B_2") (pintype "passive"))
      (node (ref "R31") (pin "2") (pinfunction "2_2") (pintype "passive"))
    )
    (net (code "47") (name "Net-(Q12-E)") (class "Default")
      (node (ref "Q12") (pin "1") (pinfunction "E_1") (pintype "passive"))
      (node (ref "R34") (pin "2") (pinfunction "2_2") (pintype "passive"))
      (node (ref "R36") (pin "2") (pinfunction "2_2") (pintype "passive"))
    )
    (net (code "48") (name "Net-(R2-Pad2)") (class "Default")
      (node (ref "R2") (pin "2") (pinfunction "2_2") (pintype "passive"))
      (node (ref "R3") (pin "1") (pinfunction "1_1") (pintype "passive"))
    )
    (net (code "49") (name "Net-(R8-Pad2)") (class "Default")
      (node (ref "R8") (pin "2") (pinfunction "2_2") (pintype "passive"))
      (node (ref "R9") (pin "1") (pinfunction "1_1") (pintype "passive"))
    )
    (net (code "50") (name "Net-(R26-Pad2)") (class "Default")
      (node (ref "R26") (pin "2") (pinfunction "2_2") (pintype "passive"))
      (node (ref "R27") (pin "1") (pinfunction "1_1") (pintype "passive"))
    )
    (net (code "51") (name "Net-(R32-Pad2)") (class "Default")
      (node (ref "R32") (pin "2") (pinfunction "2_2") (pintype "passive"))
      (node (ref "R33") (pin "1") (pinfunction "1_1") (pintype "passive"))
    )
    (net (code "52") (name "Net-(U$2M-1)") (class "Default")
      (node (ref "D24") (pin "C") (pinfunction "C_C") (pintype "passive"))
      (node (ref "U$2") (pin "P2") (pinfunction "1_P2") (pintype "bidirectional"))
    )
    (net (code "53") (name "VCC") (class "Default")
      (node (ref "C5") (pin "1") (pinfunction "1_1") (pintype "passive"))
      (node (ref "C8") (pin "1") (pinfunction "1_1") (pintype "passive"))
      (node (ref "R11") (pin "2") (pinfunction "2_2") (pintype "passive"))
      (node (ref "R25") (pin "2") (pinfunction "2_2") (pintype "passive"))
      (node (ref "R40") (pin "2") (pinfunction "2_2") (pintype "passive"))
      (node (ref "R41") (pin "2") (pinfunction "2_2") (pintype "passive"))
      (node (ref "R42") (pin "2") (pinfunction "2_2") (pintype "passive"))
      (node (ref "R7") (pin "2") (pinfunction "2_2") (pintype "passive"))
      (node (ref "U$2") (pin "A2") (pinfunction "1_A2") (pintype "bidirectional"))
    )
  )
)
